# skematik_projek_mikro.net
KiCad netlist of a schematic drawn in EAGLE
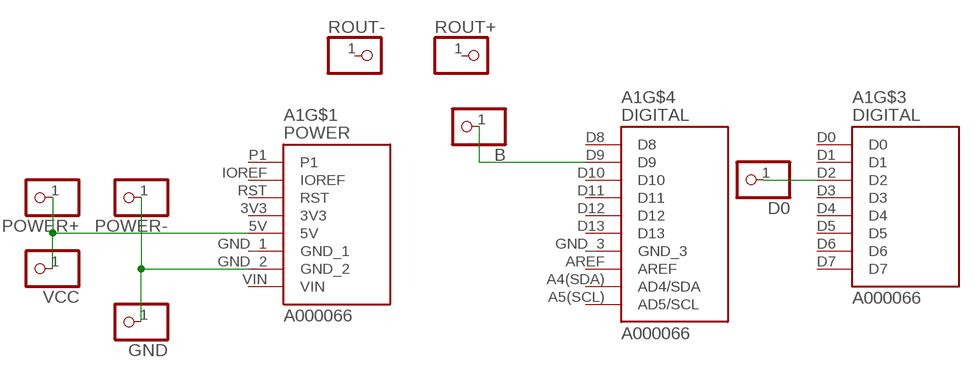
[diagram p0: schematic, sheet 1]

(export (version "E")
  (design (tool "Eeschema 10.0.6"))
  (components
    (comp (ref "A1")
      (value "A000066")
      (footprint "eagle-import:ARDUINO_A000066")
      (fields (field (name "MF") "Arduino") (field (name "MP") "ARDUINO UNO REV3"))
      (libsource (lib "eagle-import") (part "A000066"))
    )
    (comp (ref "B")
      (value "PINHD-1X1")
      (footprint "eagle-import:1X01")
      (libsource (lib "eagle-import") (part "PINHD-1X1"))
    )
    (comp (ref "D0")
      (value "PINHD-1X1")
      (footprint "eagle-import:1X01")
      (libsource (lib "eagle-import") (part "PINHD-1X1"))
    )
    (comp (ref "GND")
      (value "PINHD-1X1")
      (footprint "eagle-import:1X01")
      (libsource (lib "eagle-import") (part "PINHD-1X1"))
    )
    (comp (ref "POWER+")
      (value "PINHD-1X1")
      (footprint "eagle-import:1X01")
      (libsource (lib "eagle-import") (part "PINHD-1X1"))
    )
    (comp (ref "POWER-")
      (value "PINHD-1X1")
      (footprint "eagle-import:1X01")
      (libsource (lib "eagle-import") (part "PINHD-1X1"))
    )
    (comp (ref "ROUT+")
      (value "PINHD-1X1")
      (footprint "eagle-import:1X01")
      (libsource (lib "eagle-import") (part "PINHD-1X1"))
    )
    (comp (ref "ROUT-")
      (value "PINHD-1X1")
      (footprint "eagle-import:1X01")
      (libsource (lib "eagle-import") (part "PINHD-1X1"))
    )
    (comp (ref "VCC")
      (value "PINHD-1X1")
      (footprint "eagle-import:1X01")
      (libsource (lib "eagle-import") (part "PINHD-1X1"))
    )
  )
  (nets
    (net (code "1") (name "/3V3") (class "Default")
      (node (ref "A1") (pin "3V3") (pinfunction "3V3_3V3") (pintype "power_in"))
    )
    (net (code "2") (name "/GND_1") (class "Default")
      (node (ref "A1") (pin "GND_1") (pinfunction "GND_1_GND_1") (pintype "power_in"))
    )
    (net (code "3") (name "/GND_3") (class "Default")
      (node (ref "A1") (pin "GND_3") (pinfunction "GND_3_GND_3") (pintype "power_in"))
    )
    (net (code "4") (name "/VIN") (class "Default")
      (node (ref "A1") (pin "VIN") (pinfunction "VIN_VIN") (pintype "power_in"))
    )
    (net (code "5") (name "Net-(A1-Pad5V)") (class "Default")
      (node (ref "A1") (pin "5V") (pinfunction "5V_5V") (pintype "power_in"))
      (node (ref "POWER+") (pin "1") (pinfunction "1_1") (pintype "passive"))
      (node (ref "VCC") (pin "1") (pinfunction "1_1") (pintype "passive"))
    )
    (net (code "6") (name "Net-(A1-PadD2)") (class "Default")
      (node (ref "A1") (pin "D2") (pinfunction "D2_D2") (pintype "bidirectional"))
      (node (ref "D0") (pin "1") (pinfunction "1_1") (pintype "passive"))
    )
    (net (code "7") (name "Net-(A1-PadD9)") (class "Default")
      (node (ref "A1") (pin "D9") (pinfunction "D9_D9") (pintype "bidirectional"))
      (node (ref "B") (pin "1") (pinfunction "1_1") (pintype "passive"))
    )
    (net (code "8") (name "Net-(A1-PadGND_2)") (class "Default")
      (node (ref "A1") (pin "GND_2") (pinfunction "GND_2_GND_2") (pintype "power_in"))
      (node (ref "GND") (pin "1") (pinfunction "1_1") (pintype "passive"))
      (node (ref "POWER-") (pin "1") (pinfunction "1_1") (pintype "passive"))
    )
    (net (code "9") (name "unconnected-(A1-PadAREF)") (class "Default")
      (node (ref "A1") (pin "AREF") (pinfunction "AREF_AREF") (pintype "bidirectional"))
    )
    (net (code "10") (name "unconnected-(A1-PadD0)") (class "Default")
      (node (ref "A1") (pin "D0") (pinfunction "D0_D0") (pintype "bidirectional"))
    )
    (net (code "11") (name "unconnected-(A1-PadD1)") (class "Default")
      (node (ref "A1") (pin "D1") (pinfunction "D1_D1") (pintype "bidirectional"))
    )
    (net (code "12") (name "unconnected-(A1-PadD3)") (class "Default")
      (node (ref "A1") (pin "D3") (pinfunction "D3_D3") (pintype "bidirectional"))
    )
    (net (code "13") (name "unconnected-(A1-PadD4)") (class "Default")
      (node (ref "A1") (pin "D4") (pinfunction "D4_D4") (pintype "bidirectional"))
    )
    (net (code "14") (name "unconnected-(A1-PadD5)") (class "Default")
      (node (ref "A1") (pin "D5") (pinfunction "D5_D5") (pintype "bidirectional"))
    )
    (net (code "15") (name "unconnected-(A1-PadD6)") (class "Default")
      (node (ref "A1") (pin "D6") (pinfunction "D6_D6") (pintype "bidirectional"))
    )
    (net (code "16") (name "unconnected-(A1-PadD7)") (class "Default")
      (node (ref "A1") (pin "D7") (pinfunction "D7_D7") (pintype "bidirectional"))
    )
    (net (code "17") (name "unconnected-(A1-PadD8)") (class "Default")
      (node (ref "A1") (pin "D8") (pinfunction "D8_D8") (pintype "bidirectional"))
    )
    (net (code "18") (name "unconnected-(A1-PadD10)") (class "Default")
      (node (ref "A1") (pin "D10") (pinfunction "D10_D10") (pintype "bidirectional"))
    )
    (net (code "19") (name "unconnected-(A1-PadD11)") (class "Default")
      (node (ref "A1") (pin "D11") (pinfunction "D11_D11") (pintype "bidirectional"))
    )
    (net (code "20") (name "unconnected-(A1-PadD12)") (class "Default")
      (node (ref "A1") (pin "D12") (pinfunction "D12_D12") (pintype "bidirectional"))
    )
    (net (code "21") (name "unconnected-(A1-PadD13)") (class "Default")
      (node (ref "A1") (pin "D13") (pinfunction "D13_D13") (pintype "bidirectional"))
    )
    (net (code "22") (name "unconnected-(A1-PadIOREF)") (class "Default")
      (node (ref "A1") (pin "IOREF") (pinfunction "IOREF_IOREF") (pintype "bidirectional"))
    )
    (net (code "23") (name "unconnected-(A1-PadP1)") (class "Default")
      (node (ref "A1") (pin "P1") (pinfunction "P1_P1") (pintype "bidirectional"))
    )
    (net (code "24") (name "unconnected-(A1-PadRST)") (class "Default")
      (node (ref "A1") (pin "RST") (pinfunction "RST_RST") (pintype "bidirectional"))
    )
    (net (code "25") (name "unconnected-(A1D-AD4{slash}SDA-PadA4(SDA))") (class "Default")
      (node (ref "A1") (pin "A4(SDA)") (pinfunction "AD4/SDA_A4(SDA)") (pintype "bidirectional"))
    )
    (net (code "26") (name "unconnected-(A1D-AD5{slash}SCL-PadA5(SCL))") (class "Default")
      (node (ref "A1") (pin "A5(SCL)") (pinfunction "AD5/SCL_A5(SCL)") (pintype "bidirectional"))
    )
    (net (code "27") (name "unconnected-(ROUT+-Pad1)") (class "Default")
      (node (ref "ROUT+") (pin "1") (pinfunction "1_1") (pintype "passive"))
    )
    (net (code "28") (name "unconnected-(ROUT--Pad1)") (class "Default")
      (node (ref "ROUT-") (pin "1") (pinfunction "1_1") (pintype "passive"))
    )
  )
)
